# oresat-imu.net
KiCad netlist of a schematic drawn in EAGLE
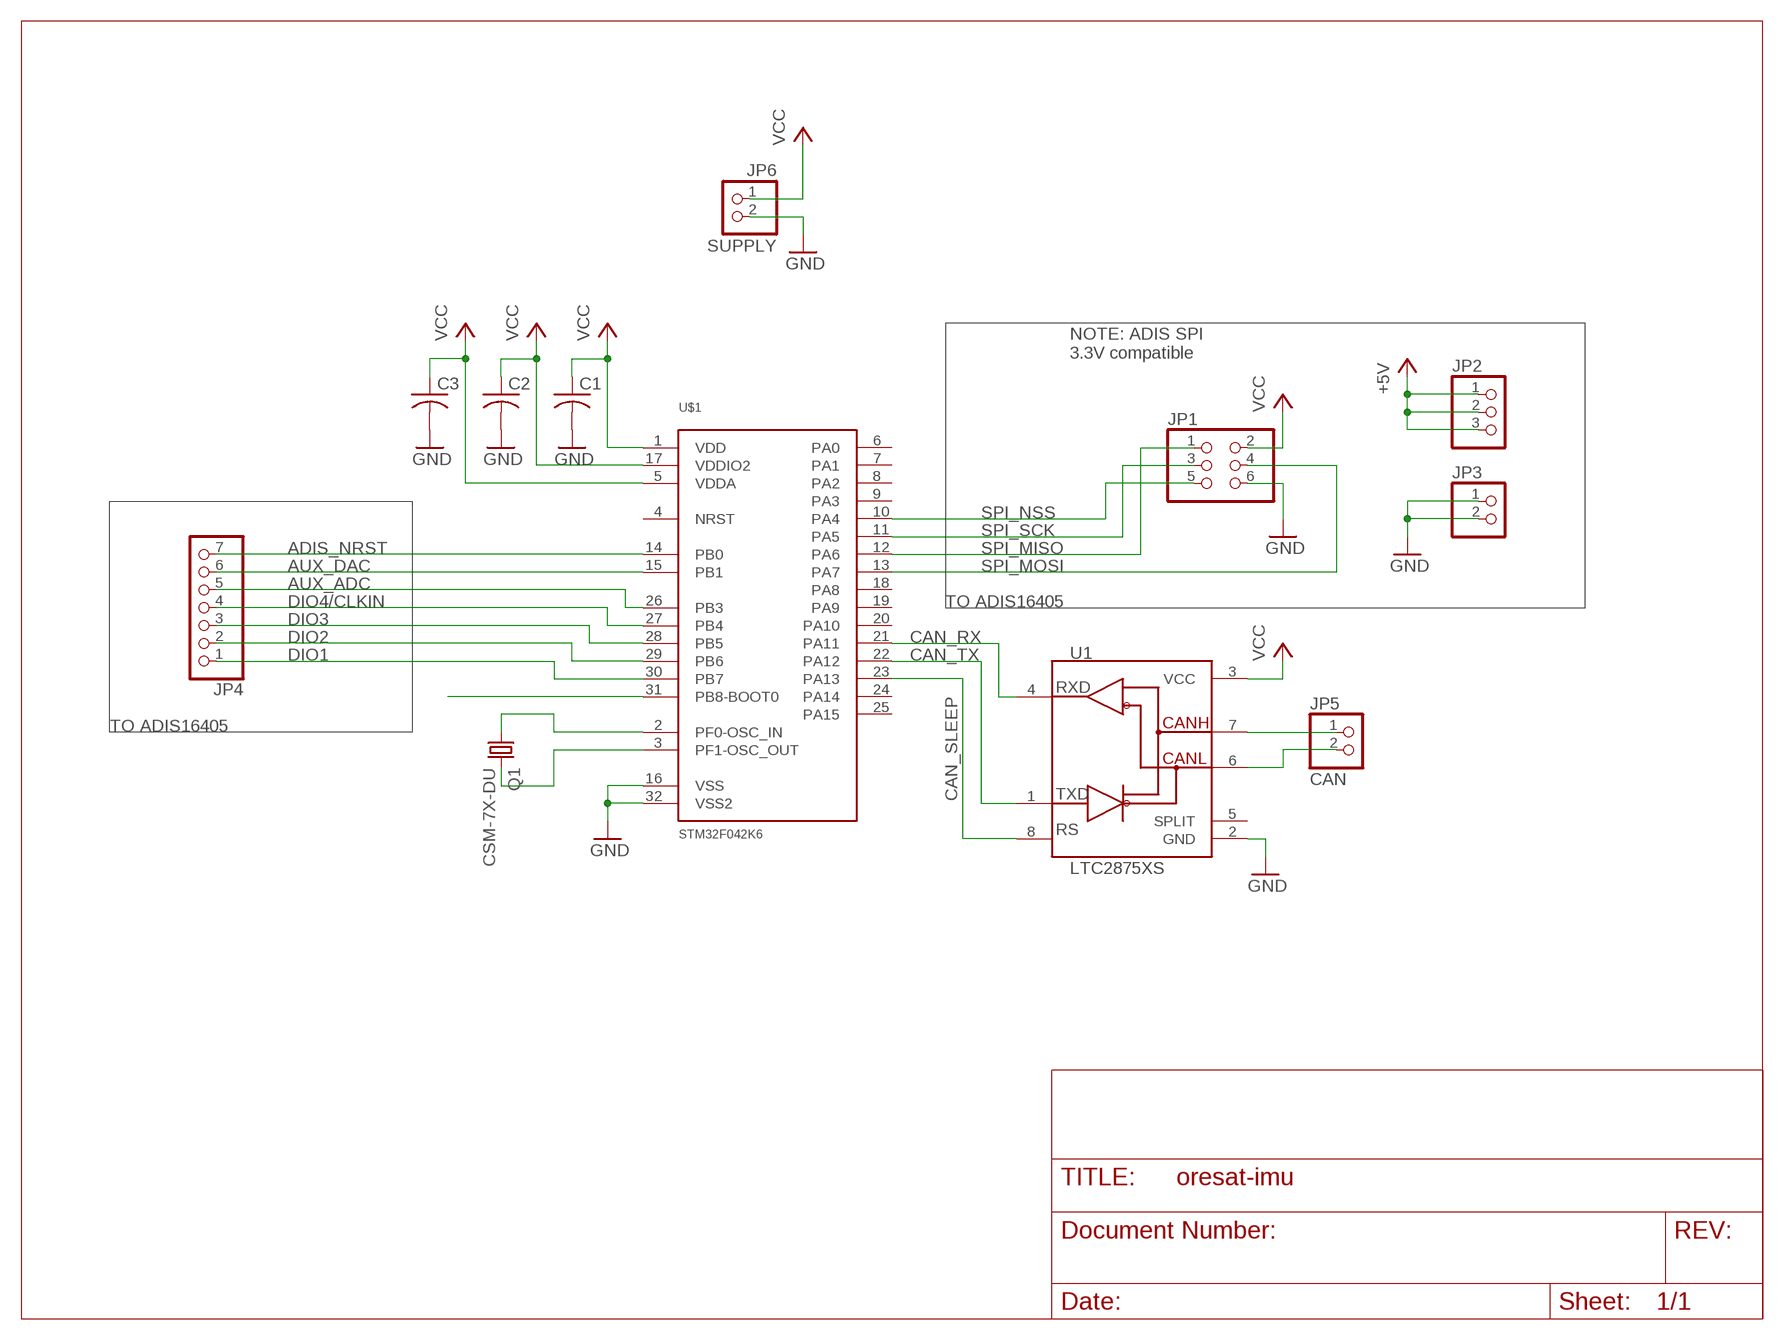
[diagram p0: schematic, sheet 1]

(export (version "E")
  (design (tool "Eeschema 10.0.6"))
  (components
    (comp (ref "C1")
      (value "C-USC0805")
      (footprint "eagle-import:C0805")
      (libsource (lib "eagle-import") (part "C-USC0805"))
    )
    (comp (ref "C2")
      (value "C-USC0805")
      (footprint "eagle-import:C0805")
      (libsource (lib "eagle-import") (part "C-USC0805"))
    )
    (comp (ref "C3")
      (value "C-USC0805")
      (footprint "eagle-import:C0805")
      (libsource (lib "eagle-import") (part "C-USC0805"))
    )
    (comp (ref "JP1")
      (value "PINHD-2X3")
      (footprint "eagle-import:2X03")
      (libsource (lib "eagle-import") (part "PINHD-2X3"))
    )
    (comp (ref "JP2")
      (value "PINHD-1X3")
      (footprint "eagle-import:1X03")
      (libsource (lib "eagle-import") (part "PINHD-1X3"))
    )
    (comp (ref "JP3")
      (value "PINHD-1X2")
      (footprint "eagle-import:1X02")
      (libsource (lib "eagle-import") (part "PINHD-1X2"))
    )
    (comp (ref "JP4")
      (value "PINHD-1X7")
      (footprint "eagle-import:1X07")
      (libsource (lib "eagle-import") (part "PINHD-1X7"))
    )
    (comp (ref "JP5")
      (value "CAN")
      (footprint "eagle-import:1X02")
      (libsource (lib "eagle-import") (part "PINHD-1X2"))
    )
    (comp (ref "JP6")
      (value "SUPPLY")
      (footprint "eagle-import:1X02_90")
      (libsource (lib "eagle-import") (part "PINHD-1X2/90"))
    )
    (comp (ref "Q1")
      (value "CSM-7X-DU")
      (footprint "eagle-import:CSM-7X-DU")
      (libsource (lib "eagle-import") (part "CSM-7X-DU"))
    )
    (comp (ref "U$1")
      (value "STM32F042K6")
      (footprint "eagle-import:LQFP32-7X7")
      (libsource (lib "eagle-import") (part "STM32F042K6"))
    )
    (comp (ref "U1")
      (value "LTC2875XS")
      (footprint "eagle-import:SO-08")
      (libsource (lib "eagle-import") (part "LTC2875XS"))
    )
  )
  (nets
    (net (code "1") (name "+5V") (class "Default")
      (node (ref "JP2") (pin "1") (pinfunction "1_1") (pintype "passive"))
      (node (ref "JP2") (pin "2") (pinfunction "2_2") (pintype "passive"))
      (node (ref "JP2") (pin "3") (pinfunction "3_3") (pintype "passive"))
    )
    (net (code "2") (name "/ADIS_NRST") (class "Default")
      (node (ref "JP4") (pin "7") (pinfunction "7_7") (pintype "passive"))
      (node (ref "U$1") (pin "14") (pinfunction "PB0_14") (pintype "bidirectional"))
    )
    (net (code "3") (name "/AUX_ADC") (class "Default")
      (node (ref "JP4") (pin "5") (pinfunction "5_5") (pintype "passive"))
      (node (ref "U$1") (pin "26") (pinfunction "PB3_26") (pintype "bidirectional"))
    )
    (net (code "4") (name "/AUX_DAC") (class "Default")
      (node (ref "JP4") (pin "6") (pinfunction "6_6") (pintype "passive"))
      (node (ref "U$1") (pin "15") (pinfunction "PB1_15") (pintype "bidirectional"))
    )
    (net (code "5") (name "/CAN_RX") (class "Default")
      (node (ref "U$1") (pin "21") (pinfunction "PA11_21") (pintype "bidirectional"))
      (node (ref "U1") (pin "4") (pinfunction "RXD_4") (pintype "bidirectional"))
    )
    (net (code "6") (name "/CAN_SLEEP") (class "Default")
      (node (ref "U$1") (pin "23") (pinfunction "PA13_23") (pintype "bidirectional"))
      (node (ref "U1") (pin "8") (pinfunction "RS1_8") (pintype "bidirectional"))
    )
    (net (code "7") (name "/CAN_TX") (class "Default")
      (node (ref "U$1") (pin "22") (pinfunction "PA12_22") (pintype "bidirectional"))
      (node (ref "U1") (pin "1") (pinfunction "TXD_1") (pintype "bidirectional"))
    )
    (net (code "8") (name "/DIO1") (class "Default")
      (node (ref "JP4") (pin "1") (pinfunction "1_1") (pintype "passive"))
      (node (ref "U$1") (pin "30") (pinfunction "PB7_30") (pintype "bidirectional"))
    )
    (net (code "9") (name "/DIO2") (class "Default")
      (node (ref "JP4") (pin "2") (pinfunction "2_2") (pintype "passive"))
      (node (ref "U$1") (pin "29") (pinfunction "PB6_29") (pintype "bidirectional"))
    )
    (net (code "10") (name "/DIO3") (class "Default")
      (node (ref "JP4") (pin "3") (pinfunction "3_3") (pintype "passive"))
      (node (ref "U$1") (pin "28") (pinfunction "PB5_28") (pintype "bidirectional"))
    )
    (net (code "11") (name "/DIO4{slash}CLKIN") (class "Default")
      (node (ref "JP4") (pin "4") (pinfunction "4_4") (pintype "passive"))
      (node (ref "U$1") (pin "27") (pinfunction "PB4_27") (pintype "bidirectional"))
    )
    (net (code "12") (name "/SPI_MISO") (class "Default")
      (node (ref "JP1") (pin "1") (pinfunction "1_1") (pintype "passive"))
      (node (ref "U$1") (pin "12") (pinfunction "PA6_12") (pintype "bidirectional"))
    )
    (net (code "13") (name "/SPI_MOSI") (class "Default")
      (node (ref "JP1") (pin "4") (pinfunction "4_4") (pintype "passive"))
      (node (ref "U$1") (pin "13") (pinfunction "PA7_13") (pintype "bidirectional"))
    )
    (net (code "14") (name "/SPI_NSS") (class "Default")
      (node (ref "JP1") (pin "5") (pinfunction "5_5") (pintype "passive"))
      (node (ref "U$1") (pin "10") (pinfunction "PA4_10") (pintype "bidirectional"))
    )
    (net (code "15") (name "/SPI_SCK") (class "Default")
      (node (ref "JP1") (pin "3") (pinfunction "3_3") (pintype "passive"))
      (node (ref "U$1") (pin "11") (pinfunction "PA5_11") (pintype "bidirectional"))
    )
    (net (code "16") (name "GND") (class "Default")
      (node (ref "C1") (pin "2") (pinfunction "2_2") (pintype "passive"))
      (node (ref "C2") (pin "2") (pinfunction "2_2") (pintype "passive"))
      (node (ref "C3") (pin "2") (pinfunction "2_2") (pintype "passive"))
      (node (ref "JP1") (pin "6") (pinfunction "6_6") (pintype "passive"))
      (node (ref "JP3") (pin "1") (pinfunction "1_1") (pintype "passive"))
      (node (ref "JP3") (pin "2") (pinfunction "2_2") (pintype "passive"))
      (node (ref "JP6") (pin "2") (pinfunction "2_2") (pintype "passive"))
      (node (ref "U$1") (pin "16") (pinfunction "VSS_16") (pintype "bidirectional"))
      (node (ref "U$1") (pin "32") (pinfunction "VSS2_32") (pintype "bidirectional"))
      (node (ref "U1") (pin "2") (pinfunction "GND_2") (pintype "bidirectional"))
    )
    (net (code "17") (name "Net-(U$1-PF0-OSC_IN)") (class "Default")
      (node (ref "Q1") (pin "1") (pinfunction "1_1") (pintype "passive"))
      (node (ref "U$1") (pin "2") (pinfunction "PF0-OSC_IN_2") (pintype "bidirectional"))
    )
    (net (code "18") (name "Net-(U$1-PF1-OSC_OUT)") (class "Default")
      (node (ref "Q1") (pin "2") (pinfunction "2_2") (pintype "passive"))
      (node (ref "U$1") (pin "3") (pinfunction "PF1-OSC_OUT_3") (pintype "bidirectional"))
    )
    (net (code "19") (name "Net-(U1-CANH)") (class "Default")
      (node (ref "JP5") (pin "1") (pinfunction "1_1") (pintype "passive"))
      (node (ref "U1") (pin "7") (pinfunction "CANH_7") (pintype "bidirectional"))
    )
    (net (code "20") (name "Net-(U1-CANL)") (class "Default")
      (node (ref "JP5") (pin "2") (pinfunction "2_2") (pintype "passive"))
      (node (ref "U1") (pin "6") (pinfunction "CANL_6") (pintype "bidirectional"))
    )
    (net (code "21") (name "VCC") (class "Default")
      (node (ref "C1") (pin "1") (pinfunction "1_1") (pintype "passive"))
      (node (ref "C2") (pin "1") (pinfunction "1_1") (pintype "passive"))
      (node (ref "C3") (pin "1") (pinfunction "1_1") (pintype "passive"))
      (node (ref "JP1") (pin "2") (pinfunction "2_2") (pintype "passive"))
      (node (ref "JP6") (pin "1") (pinfunction "1_1") (pintype "passive"))
      (node (ref "U$1") (pin "1") (pinfunction "VDD_1") (pintype "bidirectional"))
      (node (ref "U$1") (pin "17") (pinfunction "VDDIO2_17") (pintype "bidirectional"))
      (node (ref "U$1") (pin "5") (pinfunction "VDDA_5") (pintype "bidirectional"))
      (node (ref "U1") (pin "3") (pinfunction "VCC_3") (pintype "bidirectional"))
    )
    (net (code "22") (name "unconnected-(U$1-NRST-Pad4)") (class "Default")
      (node (ref "U$1") (pin "4") (pinfunction "NRST_4") (pintype "bidirectional"))
    )
    (net (code "23") (name "unconnected-(U$1-PA0-Pad6)") (class "Default")
      (node (ref "U$1") (pin "6") (pinfunction "PA0_6") (pintype "bidirectional"))
    )
    (net (code "24") (name "unconnected-(U$1-PA1-Pad7)") (class "Default")
      (node (ref "U$1") (pin "7") (pinfunction "PA1_7") (pintype "bidirectional"))
    )
    (net (code "25") (name "unconnected-(U$1-PA2-Pad8)") (class "Default")
      (node (ref "U$1") (pin "8") (pinfunction "PA2_8") (pintype "bidirectional"))
    )
    (net (code "26") (name "unconnected-(U$1-PA3-Pad9)") (class "Default")
      (node (ref "U$1") (pin "9") (pinfunction "PA3_9") (pintype "bidirectional"))
    )
    (net (code "27") (name "unconnected-(U$1-PA8-Pad18)") (class "Default")
      (node (ref "U$1") (pin "18") (pinfunction "PA8_18") (pintype "bidirectional"))
    )
    (net (code "28") (name "unconnected-(U$1-PA9-Pad19)") (class "Default")
      (node (ref "U$1") (pin "19") (pinfunction "PA9_19") (pintype "bidirectional"))
    )
    (net (code "29") (name "unconnected-(U$1-PA10-Pad20)") (class "Default")
      (node (ref "U$1") (pin "20") (pinfunction "PA10_20") (pintype "bidirectional"))
    )
    (net (code "30") (name "unconnected-(U$1-PA14-Pad24)") (class "Default")
      (node (ref "U$1") (pin "24") (pinfunction "PA14_24") (pintype "bidirectional"))
    )
    (net (code "31") (name "unconnected-(U$1-PA15-Pad25)") (class "Default")
      (node (ref "U$1") (pin "25") (pinfunction "PA15_25") (pintype "bidirectional"))
    )
    (net (code "32") (name "unconnected-(U$1-PB8-BOOT0-Pad31)") (class "Default")
      (node (ref "U$1") (pin "31") (pinfunction "PB8-BOOT0_31") (pintype "bidirectional"))
    )
    (net (code "33") (name "unconnected-(U1-SPLIT-Pad5)") (class "Default")
      (node (ref "U1") (pin "5") (pinfunction "SPLIT_5") (pintype "bidirectional"))
    )
  )
)
